# 08_LMS1_RF.net
KiCad netlist of a schematic drawn in Altium Designer
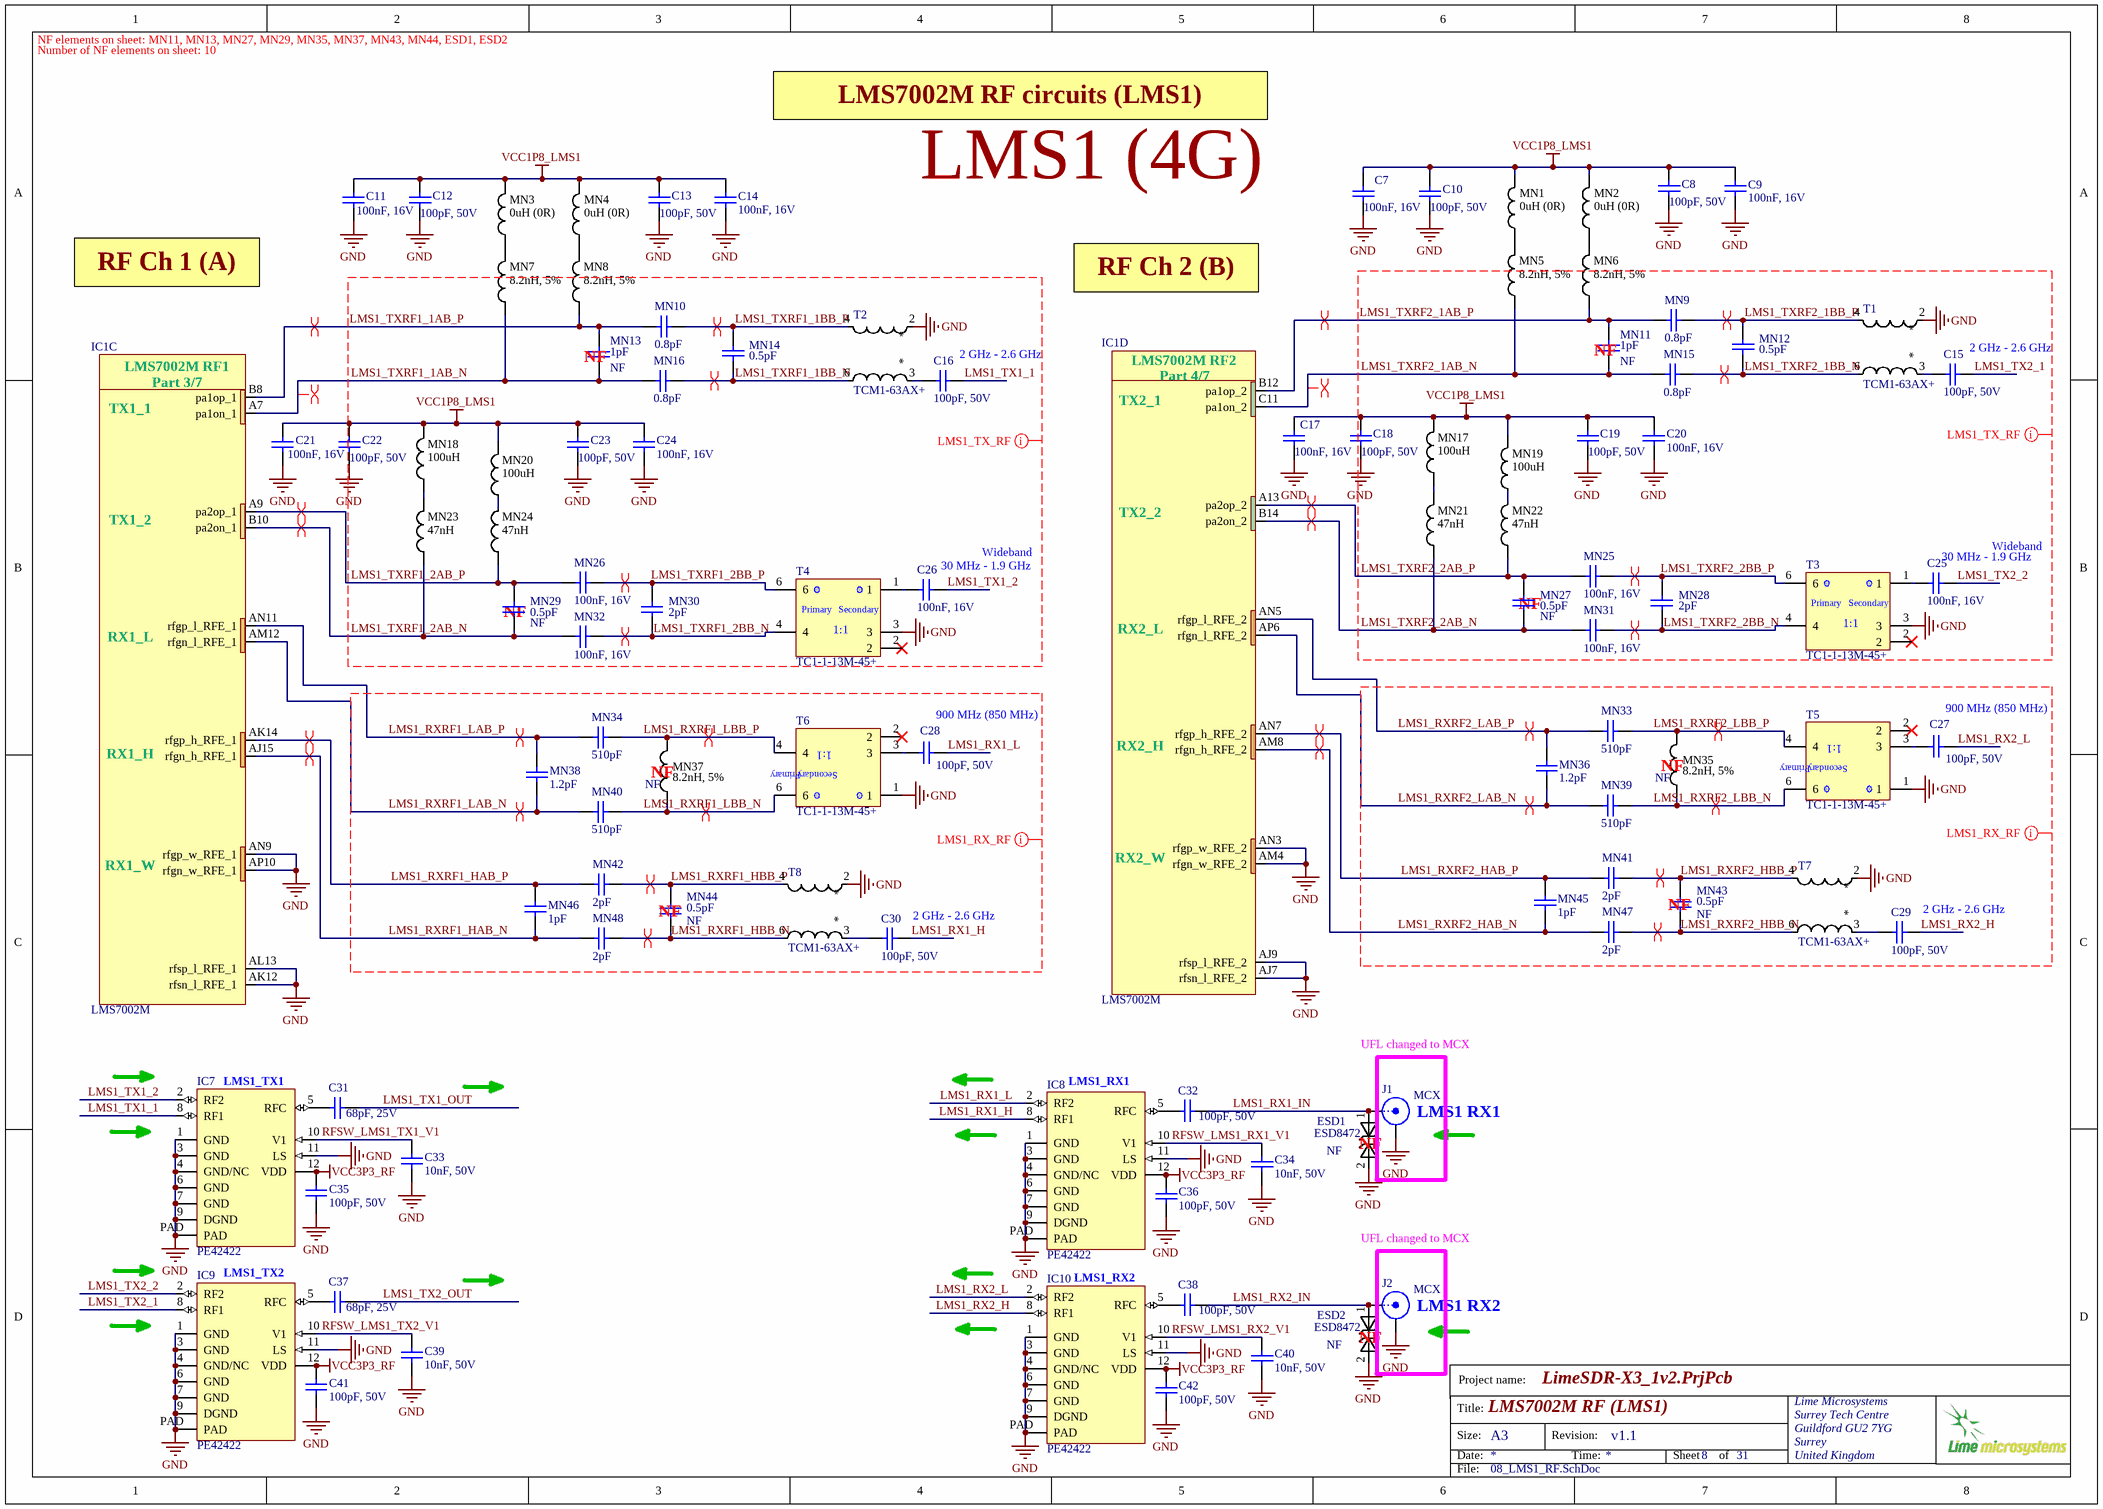
[diagram p0: 08_LMS1_RF.SchDoc]

(export (version "E")
  (design (tool "Eeschema 10.0.6"))
  (components
    (comp (ref "C7")
      (value "100nF, 16V")
      (footprint "CAP0402")
      (fields (field (name "MANUFACTURER") "Murata Electronics") (field (name "TOLERANCE") "10 %"))
      (libsource (lib "") (part "Cap_0402_2"))
    )
    (comp (ref "C8")
      (value "100pF, 50V")
      (footprint "CAP0402")
      (fields (field (name "MANUFACTURER") "Yageo") (field (name "TOLERANCE") "±5%"))
      (libsource (lib "") (part "Cap_0402_1"))
    )
    (comp (ref "C9")
      (value "100nF, 16V")
      (footprint "CAP0402")
      (fields (field (name "MANUFACTURER") "Murata Electronics") (field (name "TOLERANCE") "10 %"))
      (libsource (lib "") (part "Cap_0402_2"))
    )
    (comp (ref "C10")
      (value "100pF, 50V")
      (footprint "CAP0402")
      (fields (field (name "MANUFACTURER") "Yageo") (field (name "TOLERANCE") "±5%"))
      (libsource (lib "") (part "Cap_0402_1"))
    )
    (comp (ref "C11")
      (value "100nF, 16V")
      (footprint "CAP0402")
      (fields (field (name "MANUFACTURER") "Murata Electronics") (field (name "TOLERANCE") "10 %"))
      (libsource (lib "") (part "Cap_0402_2"))
    )
    (comp (ref "C12")
      (value "100pF, 50V")
      (footprint "CAP0402")
      (fields (field (name "MANUFACTURER") "Yageo") (field (name "TOLERANCE") "±5%"))
      (libsource (lib "") (part "Cap_0402_1"))
    )
    (comp (ref "C13")
      (value "100pF, 50V")
      (footprint "CAP0402")
      (fields (field (name "MANUFACTURER") "Yageo") (field (name "TOLERANCE") "±5%"))
      (libsource (lib "") (part "Cap_0402_1"))
    )
    (comp (ref "C14")
      (value "100nF, 16V")
      (footprint "CAP0402")
      (fields (field (name "MANUFACTURER") "Murata Electronics") (field (name "TOLERANCE") "10 %"))
      (libsource (lib "") (part "Cap_0402_2"))
    )
    (comp (ref "C15")
      (value "100pF, 50V")
      (footprint "CAP0402")
      (fields (field (name "TOLERANCE") "±5%") (field (name "MANUFACTURER") "Yageo"))
      (libsource (lib "") (part "Cap_0402_2"))
    )
    (comp (ref "C16")
      (value "100pF, 50V")
      (footprint "CAP0402")
      (fields (field (name "TOLERANCE") "±5%") (field (name "MANUFACTURER") "Yageo"))
      (libsource (lib "") (part "Cap_0402_2"))
    )
    (comp (ref "C17")
      (value "100nF, 16V")
      (footprint "CAP0402")
      (fields (field (name "MANUFACTURER") "Murata Electronics") (field (name "TOLERANCE") "10 %"))
      (libsource (lib "") (part "Cap_0402_5"))
    )
    (comp (ref "C18")
      (value "100pF, 50V")
      (footprint "CAP0402")
      (fields (field (name "MANUFACTURER") "Yageo") (field (name "TOLERANCE") "±5%"))
      (libsource (lib "") (part "Cap_0402_1"))
    )
    (comp (ref "C19")
      (value "100pF, 50V")
      (footprint "CAP0402")
      (fields (field (name "MANUFACTURER") "Yageo") (field (name "TOLERANCE") "±5%"))
      (libsource (lib "") (part "Cap_0402_1"))
    )
    (comp (ref "C20")
      (value "100nF, 16V")
      (footprint "CAP0402")
      (fields (field (name "MANUFACTURER") "Murata Electronics") (field (name "TOLERANCE") "10 %"))
      (libsource (lib "") (part "Cap_0402_5"))
    )
    (comp (ref "C21")
      (value "100nF, 16V")
      (footprint "CAP0402")
      (fields (field (name "MANUFACTURER") "Murata Electronics") (field (name "TOLERANCE") "10 %"))
      (libsource (lib "") (part "Cap_0402_5"))
    )
    (comp (ref "C22")
      (value "100pF, 50V")
      (footprint "CAP0402")
      (fields (field (name "MANUFACTURER") "Yageo") (field (name "TOLERANCE") "±5%"))
      (libsource (lib "") (part "Cap_0402_1"))
    )
    (comp (ref "C23")
      (value "100pF, 50V")
      (footprint "CAP0402")
      (fields (field (name "MANUFACTURER") "Yageo") (field (name "TOLERANCE") "±5%"))
      (libsource (lib "") (part "Cap_0402_1"))
    )
    (comp (ref "C24")
      (value "100nF, 16V")
      (footprint "CAP0402")
      (fields (field (name "MANUFACTURER") "Murata Electronics") (field (name "TOLERANCE") "10 %"))
      (libsource (lib "") (part "Cap_0402_5"))
    )
    (comp (ref "C25")
      (value "100nF, 16V")
      (footprint "CAP0402")
      (fields (field (name "MANUFACTURER") "Murata Electronics") (field (name "TOLERANCE") "10 %"))
      (libsource (lib "") (part "Cap_0402_7"))
    )
    (comp (ref "C26")
      (value "100nF, 16V")
      (footprint "CAP0402")
      (fields (field (name "MANUFACTURER") "Murata Electronics") (field (name "TOLERANCE") "10 %"))
      (libsource (lib "") (part "Cap_0402_7"))
    )
    (comp (ref "C27")
      (value "100pF, 50V")
      (footprint "CAP0402")
      (fields (field (name "TOLERANCE") "±5%") (field (name "MANUFACTURER") "Yageo"))
      (libsource (lib "") (part "Cap_0402_6"))
    )
    (comp (ref "C28")
      (value "100pF, 50V")
      (footprint "CAP0402")
      (fields (field (name "TOLERANCE") "±5%") (field (name "MANUFACTURER") "Yageo"))
      (libsource (lib "") (part "Cap_0402_6"))
    )
    (comp (ref "C29")
      (value "100pF, 50V")
      (footprint "CAP0402")
      (fields (field (name "TOLERANCE") "±5%") (field (name "MANUFACTURER") "Yageo"))
      (libsource (lib "") (part "Cap_0402_3"))
    )
    (comp (ref "C30")
      (value "100pF, 50V")
      (footprint "CAP0402")
      (fields (field (name "TOLERANCE") "±5%") (field (name "MANUFACTURER") "Yageo"))
      (libsource (lib "") (part "Cap_0402_3"))
    )
    (comp (ref "C31")
      (value "68pF, 25V")
      (footprint "CAP0402")
      (fields (field (name "TOLERANCE") "±1%") (field (name "MANUFACTURER") "Kemet"))
      (libsource (lib "") (part "Cap_0402_2"))
    )
    (comp (ref "C32")
      (value "100pF, 50V")
      (footprint "CAP0402")
      (fields (field (name "TOLERANCE") "±5%") (field (name "MANUFACTURER") "Yageo"))
      (libsource (lib "") (part "Cap_0402_4"))
    )
    (comp (ref "C33")
      (value "10nF, 50V")
      (footprint "CAP0402")
      (fields
        (field (name "MANUFACTURER") "Murata Electronics North America")
        (field (name "TOLERANCE") "±10%")
      )
      (libsource (lib "") (part "Cap_0402_2"))
    )
    (comp (ref "C34")
      (value "10nF, 50V")
      (footprint "CAP0402")
      (fields
        (field (name "MANUFACTURER") "Murata Electronics North America")
        (field (name "TOLERANCE") "±10%")
      )
      (libsource (lib "") (part "Cap_0402_10"))
    )
    (comp (ref "C35")
      (value "100pF, 50V")
      (footprint "CAP0402")
      (fields (field (name "TOLERANCE") "±5%") (field (name "MANUFACTURER") "Yageo"))
      (libsource (lib "") (part "Cap_0402_2"))
    )
    (comp (ref "C36")
      (value "100pF, 50V")
      (footprint "CAP0402")
      (fields (field (name "TOLERANCE") "±5%") (field (name "MANUFACTURER") "Yageo"))
      (libsource (lib "") (part "Cap_0402_8"))
    )
    (comp (ref "C37")
      (value "68pF, 25V")
      (footprint "CAP0402")
      (fields (field (name "TOLERANCE") "±1%") (field (name "MANUFACTURER") "Kemet"))
      (libsource (lib "") (part "Cap_0402_2"))
    )
    (comp (ref "C38")
      (value "100pF, 50V")
      (footprint "CAP0402")
      (fields (field (name "TOLERANCE") "±5%") (field (name "MANUFACTURER") "Yageo"))
      (libsource (lib "") (part "Cap_0402_4"))
    )
    (comp (ref "C39")
      (value "10nF, 50V")
      (footprint "CAP0402")
      (fields
        (field (name "MANUFACTURER") "Murata Electronics North America")
        (field (name "TOLERANCE") "±10%")
      )
      (libsource (lib "") (part "Cap_0402_2"))
    )
    (comp (ref "C40")
      (value "10nF, 50V")
      (footprint "CAP0402")
      (fields
        (field (name "MANUFACTURER") "Murata Electronics North America")
        (field (name "TOLERANCE") "±10%")
      )
      (libsource (lib "") (part "Cap_0402_10"))
    )
    (comp (ref "C41")
      (value "100pF, 50V")
      (footprint "CAP0402")
      (fields (field (name "TOLERANCE") "±5%") (field (name "MANUFACTURER") "Yageo"))
      (libsource (lib "") (part "Cap_0402_2"))
    )
    (comp (ref "C42")
      (value "100pF, 50V")
      (footprint "CAP0402")
      (fields (field (name "TOLERANCE") "±5%") (field (name "MANUFACTURER") "Yageo"))
      (libsource (lib "") (part "Cap_0402_8"))
    )
    (comp (ref "ESD1")
      (value "ESD8472")
      (footprint "ESD8472_X3DFN2")
      (fields (field (name "MANUFACTURER") "ON Semiconductor") (field (name "ASSEMBLY INFO") "NF"))
      (libsource (lib "LimeMicroAltiumLib_schLib") (part "ESD8472"))
    )
    (comp (ref "ESD2")
      (value "ESD8472")
      (footprint "ESD8472_X3DFN2")
      (fields (field (name "MANUFACTURER") "ON Semiconductor") (field (name "ASSEMBLY INFO") "NF"))
      (libsource (lib "LimeMicroAltiumLib_schLib") (part "ESD8472"))
    )
    (comp (ref "IC1")
      (value "LMS7002M")
      (footprint "LMS7002M_v5")
      (description "Schematic symbol revision 4. Default footprint - 0.31mm pad")
      (fields (field (name "MANUFACTURER") "Lime Microsystems"))
      (libsource (lib "LimeMicroAltiumLib_schLib_r04") (part "LMS7002Mr4"))
    )
    (comp (ref "IC7")
      (value "PE42422")
      (footprint "PE42422_QFN12")
      (fields (field (name "MANUFACTURER") "Peregrine Semiconductor"))
      (libsource (lib "") (part "PE42422_1"))
    )
    (comp (ref "IC8")
      (value "PE42422")
      (footprint "PE42422_QFN12")
      (fields (field (name "MANUFACTURER") "Peregrine Semiconductor"))
      (libsource (lib "LimeMicroAltiumLib_schLib") (part "PE42422"))
    )
    (comp (ref "IC9")
      (value "PE42422")
      (footprint "PE42422_QFN12")
      (fields (field (name "MANUFACTURER") "Peregrine Semiconductor"))
      (libsource (lib "") (part "PE42422_1"))
    )
    (comp (ref "IC10")
      (value "PE42422")
      (footprint "PE42422_QFN12")
      (fields (field (name "MANUFACTURER") "Peregrine Semiconductor"))
      (libsource (lib "LimeMicroAltiumLib_schLib") (part "PE42422"))
    )
    (comp (ref "J1")
      (value "MCX")
      (footprint "MCX_connector_vertical_SM")
      (description "Conn MCX RCP 0Hz to 6GHz 50Ohm Solder ST SMD Gold Over Nickel Stock")
      (fields (field (name "MANUFACTURER") "Bel Cinch"))
      (libsource (lib "LimeMicroAltiumLib_schLib") (part "RF_IF_connector"))
    )
    (comp (ref "J2")
      (value "MCX")
      (footprint "MCX_connector_vertical_SM")
      (description "Conn MCX RCP 0Hz to 6GHz 50Ohm Solder ST SMD Gold Over Nickel Stock")
      (fields (field (name "MANUFACTURER") "Bel Cinch"))
      (libsource (lib "LimeMicroAltiumLib_schLib") (part "RF_IF_connector"))
    )
    (comp (ref "MN1")
      (value "0uH (0R)")
      (footprint "RES0603")
      (fields
        (field (name "MANUFACTURER") "Panasonic Electronic Components")
        (field (name "MANUFACTURER PART NUMBER") "ERJ-3GEY0R00V")
        (field (name "TOLERANCE") "Jumper")
      )
      (libsource (lib "LimeMicroAltiumLib_schLib") (part "Inductor_0603"))
    )
    (comp (ref "MN2")
      (value "0uH (0R)")
      (footprint "RES0603")
      (fields
        (field (name "MANUFACTURER") "Panasonic Electronic Components")
        (field (name "MANUFACTURER PART NUMBER") "ERJ-3GEY0R00V")
        (field (name "TOLERANCE") "Jumper")
      )
      (libsource (lib "LimeMicroAltiumLib_schLib") (part "Inductor_0603"))
    )
    (comp (ref "MN3")
      (value "0uH (0R)")
      (footprint "RES0603")
      (fields
        (field (name "MANUFACTURER") "Panasonic Electronic Components")
        (field (name "MANUFACTURER PART NUMBER") "ERJ-3GEY0R00V")
        (field (name "TOLERANCE") "Jumper")
      )
      (libsource (lib "LimeMicroAltiumLib_schLib") (part "Inductor_0603"))
    )
    (comp (ref "MN4")
      (value "0uH (0R)")
      (footprint "RES0603")
      (fields
        (field (name "MANUFACTURER") "Panasonic Electronic Components")
        (field (name "MANUFACTURER PART NUMBER") "ERJ-3GEY0R00V")
        (field (name "TOLERANCE") "Jumper")
      )
      (libsource (lib "LimeMicroAltiumLib_schLib") (part "Inductor_0603"))
    )
    (comp (ref "MN5")
      (value "8.2nH, 5%")
      (footprint "RES0402")
      (fields (field (name "MANUFACTURER") "COILCRAFT"))
      (libsource (lib "") (part "Inductor_0603_1"))
    )
    (comp (ref "MN6")
      (value "8.2nH, 5%")
      (footprint "RES0402")
      (fields (field (name "MANUFACTURER") "COILCRAFT"))
      (libsource (lib "") (part "Inductor_0603_1"))
    )
    (comp (ref "MN7")
      (value "8.2nH, 5%")
      (footprint "RES0402")
      (fields (field (name "MANUFACTURER") "COILCRAFT"))
      (libsource (lib "") (part "Inductor_0603_1"))
    )
    (comp (ref "MN8")
      (value "8.2nH, 5%")
      (footprint "RES0402")
      (fields (field (name "MANUFACTURER") "COILCRAFT"))
      (libsource (lib "") (part "Inductor_0603_1"))
    )
    (comp (ref "MN9")
      (value "0.8pF")
      (footprint "CAP0402")
      (fields
        (field (name "TOLERANCE") "±0.1pF")
        (field (name "MANUFACTURER") "Murata Electronics North America")
        (field (name "MANUFACTURER PART NUMBER") "GRM1555C1HR80BA01D")
      )
      (libsource (lib "LimeMicroAltiumLib_schLib") (part "Cap_0402"))
    )
    (comp (ref "MN10")
      (value "0.8pF")
      (footprint "CAP0402")
      (fields
        (field (name "TOLERANCE") "±0.1pF")
        (field (name "MANUFACTURER") "Murata Electronics North America")
        (field (name "MANUFACTURER PART NUMBER") "GRM1555C1HR80BA01D")
      )
      (libsource (lib "LimeMicroAltiumLib_schLib") (part "Cap_0402"))
    )
    (comp (ref "MN11")
      (value "1pF")
      (footprint "CAP0402")
      (fields
        (field (name "ASSEMBLY INFO") "NF")
        (field (name "MANUFACTURER") "TDK Corporation")
        (field (name "TOLERANCE") "±0.1pF")
      )
      (libsource (lib "") (part "Cap_0402_6"))
    )
    (comp (ref "MN12")
      (value "0.5pF")
      (footprint "CAP0402")
      (fields (field (name "TOLERANCE") "±0.25pF") (field (name "MANUFACTURER") "Yageo"))
      (libsource (lib "") (part "Cap_0402_9"))
    )
    (comp (ref "MN13")
      (value "1pF")
      (footprint "CAP0402")
      (fields
        (field (name "ASSEMBLY INFO") "NF")
        (field (name "MANUFACTURER") "TDK Corporation")
        (field (name "TOLERANCE") "±0.1pF")
      )
      (libsource (lib "") (part "Cap_0402_6"))
    )
    (comp (ref "MN14")
      (value "0.5pF")
      (footprint "CAP0402")
      (fields (field (name "TOLERANCE") "±0.25pF") (field (name "MANUFACTURER") "Yageo"))
      (libsource (lib "") (part "Cap_0402_9"))
    )
    (comp (ref "MN15")
      (value "0.8pF")
      (footprint "CAP0402")
      (fields
        (field (name "TOLERANCE") "±0.1pF")
        (field (name "MANUFACTURER") "Murata Electronics North America")
        (field (name "MANUFACTURER PART NUMBER") "GRM1555C1HR80BA01D")
      )
      (libsource (lib "LimeMicroAltiumLib_schLib") (part "Cap_0402"))
    )
    (comp (ref "MN16")
      (value "0.8pF")
      (footprint "CAP0402")
      (fields
        (field (name "TOLERANCE") "±0.1pF")
        (field (name "MANUFACTURER") "Murata Electronics North America")
        (field (name "MANUFACTURER PART NUMBER") "GRM1555C1HR80BA01D")
      )
      (libsource (lib "LimeMicroAltiumLib_schLib") (part "Cap_0402"))
    )
    (comp (ref "MN17")
      (value "100uH")
      (footprint "RES0603")
      (fields
        (field (name "MANUFACTURER") "TDK Corporation")
        (field (name "MANUFACTURER PART NUMBER") "GLFR1608T101M-LR")
        (field (name "TOLERANCE") "±20%")
      )
      (libsource (lib "LimeMicroAltiumLib_schLib") (part "Inductor_0603"))
    )
    (comp (ref "MN18")
      (value "100uH")
      (footprint "RES0603")
      (fields
        (field (name "MANUFACTURER") "TDK Corporation")
        (field (name "MANUFACTURER PART NUMBER") "GLFR1608T101M-LR")
        (field (name "TOLERANCE") "±20%")
      )
      (libsource (lib "LimeMicroAltiumLib_schLib") (part "Inductor_0603"))
    )
    (comp (ref "MN19")
      (value "100uH")
      (footprint "RES0603")
      (fields
        (field (name "MANUFACTURER") "TDK Corporation")
        (field (name "MANUFACTURER PART NUMBER") "GLFR1608T101M-LR")
        (field (name "TOLERANCE") "±20%")
      )
      (libsource (lib "LimeMicroAltiumLib_schLib") (part "Inductor_0603"))
    )
    (comp (ref "MN20")
      (value "100uH")
      (footprint "RES0603")
      (fields
        (field (name "MANUFACTURER") "TDK Corporation")
        (field (name "MANUFACTURER PART NUMBER") "GLFR1608T101M-LR")
        (field (name "TOLERANCE") "±20%")
      )
      (libsource (lib "LimeMicroAltiumLib_schLib") (part "Inductor_0603"))
    )
    (comp (ref "MN21")
      (value "47nH")
      (footprint "RES0402")
      (fields (field (name "MANUFACTURER") "COILCRAFT"))
      (libsource (lib "") (part "Inductor_0603_2"))
    )
    (comp (ref "MN22")
      (value "47nH")
      (footprint "RES0402")
      (fields (field (name "MANUFACTURER") "COILCRAFT"))
      (libsource (lib "") (part "Inductor_0603_2"))
    )
    (comp (ref "MN23")
      (value "47nH")
      (footprint "RES0402")
      (fields (field (name "MANUFACTURER") "COILCRAFT"))
      (libsource (lib "") (part "Inductor_0603_2"))
    )
    (comp (ref "MN24")
      (value "47nH")
      (footprint "RES0402")
      (fields (field (name "MANUFACTURER") "COILCRAFT"))
      (libsource (lib "") (part "Inductor_0603_2"))
    )
    (comp (ref "MN25")
      (value "100nF, 16V")
      (footprint "CAP0402")
      (fields (field (name "MANUFACTURER") "Murata Electronics") (field (name "TOLERANCE") "10 %"))
      (libsource (lib "") (part "Cap_0402_1"))
    )
    (comp (ref "MN26")
      (value "100nF, 16V")
      (footprint "CAP0402")
      (fields (field (name "MANUFACTURER") "Murata Electronics") (field (name "TOLERANCE") "10 %"))
      (libsource (lib "") (part "Cap_0402_1"))
    )
    (comp (ref "MN27")
      (value "0.5pF")
      (footprint "CAP0402")
      (fields
        (field (name "ASSEMBLY INFO") "NF")
        (field (name "TOLERANCE") "±0.25pF")
        (field (name "MANUFACTURER") "Yageo")
      )
      (libsource (lib "") (part "Cap_0402_5"))
    )
    (comp (ref "MN28")
      (value "2pF")
      (footprint "CAP0402")
      (fields (field (name "MANUFACTURER PART NUMBER") "04025U2R0BAT2A") (field (name "MANUFACTURER") "AVX"))
      (libsource (lib "") (part "Cap_0402_5"))
    )
    (comp (ref "MN29")
      (value "0.5pF")
      (footprint "CAP0402")
      (fields
        (field (name "ASSEMBLY INFO") "NF")
        (field (name "TOLERANCE") "±0.25pF")
        (field (name "MANUFACTURER") "Yageo")
      )
      (libsource (lib "") (part "Cap_0402_5"))
    )
    (comp (ref "MN30")
      (value "2pF")
      (footprint "CAP0402")
      (fields (field (name "MANUFACTURER PART NUMBER") "04025U2R0BAT2A") (field (name "MANUFACTURER") "AVX"))
      (libsource (lib "") (part "Cap_0402_5"))
    )
    (comp (ref "MN31")
      (value "100nF, 16V")
      (footprint "CAP0402")
      (fields (field (name "MANUFACTURER") "Murata Electronics") (field (name "TOLERANCE") "10 %"))
      (libsource (lib "") (part "Cap_0402_9"))
    )
    (comp (ref "MN32")
      (value "100nF, 16V")
      (footprint "CAP0402")
      (fields (field (name "MANUFACTURER") "Murata Electronics") (field (name "TOLERANCE") "10 %"))
      (libsource (lib "") (part "Cap_0402_9"))
    )
    (comp (ref "MN33")
      (value "510pF")
      (footprint "CAP0402")
      (fields
        (field (name "TOLERANCE") "±5%")
        (field (name "MANUFACTURER") "Murata Electronics North America")
      )
      (libsource (lib "") (part "Cap_0402_2"))
    )
    (comp (ref "MN34")
      (value "510pF")
      (footprint "CAP0402")
      (fields
        (field (name "TOLERANCE") "±5%")
        (field (name "MANUFACTURER") "Murata Electronics North America")
      )
      (libsource (lib "") (part "Cap_0402_2"))
    )
    (comp (ref "MN35")
      (value "8.2nH, 5%")
      (footprint "RES0402")
      (fields (field (name "MANUFACTURER") "COILCRAFT") (field (name "ASSEMBLY INFO") "NF"))
      (libsource (lib "") (part "Inductor_0603_2"))
    )
    (comp (ref "MN36")
      (value "1.2pF")
      (footprint "CAP0402")
      (fields
        (field (name "MANUFACTURER") "Murata Electronics North America")
        (field (name "TOLERANCE") "±0.25pF")
      )
      (libsource (lib "") (part "Cap_0402_2"))
    )
    (comp (ref "MN37")
      (value "8.2nH, 5%")
      (footprint "RES0402")
      (fields (field (name "MANUFACTURER") "COILCRAFT") (field (name "ASSEMBLY INFO") "NF"))
      (libsource (lib "") (part "Inductor_0603_2"))
    )
    (comp (ref "MN38")
      (value "1.2pF")
      (footprint "CAP0402")
      (fields
        (field (name "MANUFACTURER") "Murata Electronics North America")
        (field (name "TOLERANCE") "±0.25pF")
      )
      (libsource (lib "") (part "Cap_0402_2"))
    )
    (comp (ref "MN39")
      (value "510pF")
      (footprint "CAP0402")
      (fields
        (field (name "TOLERANCE") "±5%")
        (field (name "MANUFACTURER") "Murata Electronics North America")
      )
      (libsource (lib "") (part "Cap_0402_2"))
    )
    (comp (ref "MN40")
      (value "510pF")
      (footprint "CAP0402")
      (fields
        (field (name "TOLERANCE") "±5%")
        (field (name "MANUFACTURER") "Murata Electronics North America")
      )
      (libsource (lib "") (part "Cap_0402_2"))
    )
    (comp (ref "MN41")
      (value "2pF")
      (footprint "CAP0402")
      (fields (field (name "MANUFACTURER PART NUMBER") "04025U2R0BAT2A") (field (name "MANUFACTURER") "AVX"))
      (libsource (lib "LimeMicroAltiumLib_schLib") (part "Cap_0402"))
    )
    (comp (ref "MN42")
      (value "2pF")
      (footprint "CAP0402")
      (fields (field (name "MANUFACTURER PART NUMBER") "04025U2R0BAT2A") (field (name "MANUFACTURER") "AVX"))
      (libsource (lib "LimeMicroAltiumLib_schLib") (part "Cap_0402"))
    )
    (comp (ref "MN43")
      (value "0.5pF")
      (footprint "CAP0402")
      (fields
        (field (name "ASSEMBLY INFO") "NF")
        (field (name "TOLERANCE") "±0.25pF")
        (field (name "MANUFACTURER") "Yageo")
      )
      (libsource (lib "LimeMicroAltiumLib_schLib") (part "Cap_0402"))
    )
    (comp (ref "MN44")
      (value "0.5pF")
      (footprint "CAP0402")
      (fields
        (field (name "ASSEMBLY INFO") "NF")
        (field (name "TOLERANCE") "±0.25pF")
        (field (name "MANUFACTURER") "Yageo")
      )
      (libsource (lib "LimeMicroAltiumLib_schLib") (part "Cap_0402"))
    )
    (comp (ref "MN45")
      (value "1pF")
      (footprint "CAP0402")
      (fields (field (name "MANUFACTURER") "TDK Corporation") (field (name "TOLERANCE") "±0.1pF"))
      (libsource (lib "LimeMicroAltiumLib_schLib") (part "Cap_0402"))
    )
    (comp (ref "MN46")
      (value "1pF")
      (footprint "CAP0402")
      (fields (field (name "MANUFACTURER") "TDK Corporation") (field (name "TOLERANCE") "±0.1pF"))
      (libsource (lib "LimeMicroAltiumLib_schLib") (part "Cap_0402"))
    )
    (comp (ref "MN47")
      (value "2pF")
      (footprint "CAP0402")
      (fields (field (name "MANUFACTURER PART NUMBER") "04025U2R0BAT2A") (field (name "MANUFACTURER") "AVX"))
      (libsource (lib "LimeMicroAltiumLib_schLib") (part "Cap_0402"))
    )
    (comp (ref "MN48")
      (value "2pF")
      (footprint "CAP0402")
      (fields (field (name "MANUFACTURER PART NUMBER") "04025U2R0BAT2A") (field (name "MANUFACTURER") "AVX"))
      (libsource (lib "LimeMicroAltiumLib_schLib") (part "Cap_0402"))
    )
    (comp (ref "T1")
      (value "TCM1-63AX+")
      (footprint "TCM1-63AX+_v2")
      (fields (field (name "MANUFACTURER") "Mini-circuits"))
      (libsource (lib "") (part "Balun_v2_1"))
    )
    (comp (ref "T2")
      (value "TCM1-63AX+")
      (footprint "TCM1-63AX+_v2")
      (fields (field (name "MANUFACTURER") "Mini-circuits"))
      (libsource (lib "") (part "Balun_v2_1"))
    )
    (comp (ref "T3")
      (value "TC1-1-13M-45+")
      (footprint "TC1-1-13MA+_JA4220-AL_")
      (fields (field (name "MANUFACTURER") "Minicircuits"))
      (libsource (lib "") (part "TC1-1-13M+_1"))
    )
    (comp (ref "T4")
      (value "TC1-1-13M-45+")
      (footprint "TC1-1-13MA+_JA4220-AL_")
      (fields (field (name "MANUFACTURER") "Minicircuits"))
      (libsource (lib "") (part "TC1-1-13M+_1"))
    )
    (comp (ref "T5")
      (value "TC1-1-13M-45+")
      (footprint "TC1-1-13MA+_JA4220-AL_")
      (fields (field (name "MANUFACTURER") "Minicircuits"))
      (libsource (lib "LimeMicroAltiumLib_schLib") (part "TC1-1-13M+"))
    )
    (comp (ref "T6")
      (value "TC1-1-13M-45+")
      (footprint "TC1-1-13MA+_JA4220-AL_")
      (fields (field (name "MANUFACTURER") "Minicircuits"))
      (libsource (lib "LimeMicroAltiumLib_schLib") (part "TC1-1-13M+"))
    )
    (comp (ref "T7")
      (value "TCM1-63AX+")
      (footprint "TCM1-63AX+_v2")
      (fields (field (name "MANUFACTURER") "Mini-circuits"))
      (libsource (lib "LimeMicroAltiumLib_schLib") (part "Balun_v2"))
    )
    (comp (ref "T8")
      (value "TCM1-63AX+")
      (footprint "TCM1-63AX+_v2")
      (fields (field (name "MANUFACTURER") "Mini-circuits"))
      (libsource (lib "LimeMicroAltiumLib_schLib") (part "Balun_v2"))
    )
  )
  (nets
    (net (code "1") (name "/LMS1_RX1_H") (class "Default")
      (node (ref "C30") (pin "1") (pinfunction "1_1") (pintype "passive"))
      (node (ref "IC8") (pin "8") (pinfunction "RF1_8") (pintype "bidirectional"))
    )
    (net (code "2") (name "/LMS1_RX1_IN") (class "Default")
      (node (ref "C32") (pin "1") (pinfunction "1_1") (pintype "passive"))
      (node (ref "ESD1") (pin "1") (pinfunction "1_1") (pintype "passive"))
      (node (ref "J1") (pin "1") (pinfunction "X_1") (pintype "passive"))
    )
    (net (code "3") (name "/LMS1_RX1_L") (class "Default")
      (node (ref "C28") (pin "1") (pinfunction "1_1") (pintype "passive"))
      (node (ref "IC8") (pin "2") (pinfunction "RF2_2") (pintype "bidirectional"))
    )
    (net (code "4") (name "/LMS1_RX2_H") (class "Default")
      (node (ref "C29") (pin "1") (pinfunction "1_1") (pintype "passive"))
      (node (ref "IC10") (pin "8") (pinfunction "RF1_8") (pintype "bidirectional"))
    )
    (net (code "5") (name "/LMS1_RX2_IN") (class "Default")
      (node (ref "C38") (pin "1") (pinfunction "1_1") (pintype "passive"))
      (node (ref "ESD2") (pin "1") (pinfunction "1_1") (pintype "passive"))
      (node (ref "J2") (pin "1") (pinfunction "X_1") (pintype "passive"))
    )
    (net (code "6") (name "/LMS1_RX2_L") (class "Default")
      (node (ref "C27") (pin "1") (pinfunction "1_1") (pintype "passive"))
      (node (ref "IC10") (pin "2") (pinfunction "RF2_2") (pintype "bidirectional"))
    )
    (net (code "7") (name "/LMS1_RXRF1_HAB_N") (class "Default")
      (node (ref "IC1") (pin "AJ15") (pinfunction "rfgn_h_RFE_1_AJ15") (pintype "passive"))
      (node (ref "MN46") (pin "1") (pinfunction "1_1") (pintype "passive"))
      (node (ref "MN48") (pin "2") (pinfunction "2_2") (pintype "passive"))
    )
    (net (code "8") (name "/LMS1_RXRF1_HAB_P") (class "Default")
      (node (ref "IC1") (pin "AK14") (pinfunction "rfgp_h_RFE_1_AK14") (pintype "passive"))
      (node (ref "MN42") (pin "2") (pinfunction "2_2") (pintype "passive"))
      (node (ref "MN46") (pin "2") (pinfunction "2_2") (pintype "passive"))
    )
    (net (code "9") (name "/LMS1_RXRF1_HBB_N") (class "Default")
      (node (ref "MN44") (pin "1") (pinfunction "1_1") (pintype "passive"))
      (node (ref "MN48") (pin "1") (pinfunction "1_1") (pintype "passive"))
      (node (ref "T8") (pin "6") (pinfunction "6_6") (pintype "passive"))
    )
    (net (code "10") (name "/LMS1_RXRF1_HBB_P") (class "Default")
      (node (ref "MN42") (pin "1") (pinfunction "1_1") (pintype "passive"))
      (node (ref "MN44") (pin "2") (pinfunction "2_2") (pintype "passive"))
      (node (ref "T8") (pin "4") (pinfunction "4_4") (pintype "passive"))
    )
    (net (code "11") (name "/LMS1_RXRF1_LAB_N") (class "Default")
      (node (ref "IC1") (pin "AM12") (pinfunction "rfgn_l_RFE_1_AM12") (pintype "passive"))
      (node (ref "MN38") (pin "1") (pinfunction "1_1") (pintype "passive"))
      (node (ref "MN40") (pin "2") (pinfunction "2_2") (pintype "passive"))
    )
    (net (code "12") (name "/LMS1_RXRF1_LAB_P") (class "Default")
      (node (ref "IC1") (pin "AN11") (pinfunction "rfgp_l_RFE_1_AN11") (pintype "passive"))
      (node (ref "MN34") (pin "2") (pinfunction "2_2") (pintype "passive"))
      (node (ref "MN38") (pin "2") (pinfunction "2_2") (pintype "passive"))
    )
    (net (code "13") (name "/LMS1_RXRF1_LBB_N") (class "Default")
      (node (ref "MN37") (pin "1") (pinfunction "1_1") (pintype "passive"))
      (node (ref "MN40") (pin "1") (pinfunction "1_1") (pintype "passive"))
      (node (ref "T6") (pin "6") (pinfunction "6_6") (pintype "passive"))
    )
    (net (code "14") (name "/LMS1_RXRF1_LBB_P") (class "Default")
      (node (ref "MN34") (pin "1") (pinfunction "1_1") (pintype "passive"))
      (node (ref "MN37") (pin "2") (pinfunction "2_2") (pintype "passive"))
      (node (ref "T6") (pin "4") (pinfunction "4_4") (pintype "passive"))
    )
    (net (code "15") (name "/LMS1_RXRF2_HAB_N") (class "Default")
      (node (ref "IC1") (pin "AM8") (pinfunction "rfgn_h_RFE_2_AM8") (pintype "passive"))
      (node (ref "MN45") (pin "1") (pinfunction "1_1") (pintype "passive"))
      (node (ref "MN47") (pin "2") (pinfunction "2_2") (pintype "passive"))
    )
    (net (code "16") (name "/LMS1_RXRF2_HAB_P") (class "Default")
      (node (ref "IC1") (pin "AN7") (pinfunction "rfgp_h_RFE_2_AN7") (pintype "passive"))
      (node (ref "MN41") (pin "2") (pinfunction "2_2") (pintype "passive"))
      (node (ref "MN45") (pin "2") (pinfunction "2_2") (pintype "passive"))
    )
    (net (code "17") (name "/LMS1_RXRF2_HBB_N") (class "Default")
      (node (ref "MN43") (pin "1") (pinfunction "1_1") (pintype "passive"))
      (node (ref "MN47") (pin "1") (pinfunction "1_1") (pintype "passive"))
      (node (ref "T7") (pin "6") (pinfunction "6_6") (pintype "passive"))
    )
    (net (code "18") (name "/LMS1_RXRF2_HBB_P") (class "Default")
      (node (ref "MN41") (pin "1") (pinfunction "1_1") (pintype "passive"))
      (node (ref "MN43") (pin "2") (pinfunction "2_2") (pintype "passive"))
      (node (ref "T7") (pin "4") (pinfunction "4_4") (pintype "passive"))
    )
    (net (code "19") (name "/LMS1_RXRF2_LAB_N") (class "Default")
      (node (ref "IC1") (pin "AP6") (pinfunction "rfgn_l_RFE_2_AP6") (pintype "passive"))
      (node (ref "MN36") (pin "1") (pinfunction "1_1") (pintype "passive"))
      (node (ref "MN39") (pin "2") (pinfunction "2_2") (pintype "passive"))
    )
    (net (code "20") (name "/LMS1_RXRF2_LAB_P") (class "Default")
      (node (ref "IC1") (pin "AN5") (pinfunction "rfgp_l_RFE_2_AN5") (pintype "passive"))
      (node (ref "MN33") (pin "2") (pinfunction "2_2") (pintype "passive"))
      (node (ref "MN36") (pin "2") (pinfunction "2_2") (pintype "passive"))
    )
    (net (code "21") (name "/LMS1_RXRF2_LBB_N") (class "Default")
      (node (ref "MN35") (pin "1") (pinfunction "1_1") (pintype "passive"))
      (node (ref "MN39") (pin "1") (pinfunction "1_1") (pintype "passive"))
      (node (ref "T5") (pin "6") (pinfunction "6_6") (pintype "passive"))
    )
    (net (code "22") (name "/LMS1_RXRF2_LBB_P") (class "Default")
      (node (ref "MN33") (pin "1") (pinfunction "1_1") (pintype "passive"))
      (node (ref "MN35") (pin "2") (pinfunction "2_2") (pintype "passive"))
      (node (ref "T5") (pin "4") (pinfunction "4_4") (pintype "passive"))
    )
    (net (code "23") (name "/LMS1_TX1_1") (class "Default")
      (node (ref "C16") (pin "1") (pinfunction "1_1") (pintype "passive"))
      (node (ref "IC7") (pin "8") (pinfunction "RF1_8") (pintype "bidirectional"))
    )
    (net (code "24") (name "/LMS1_TX1_2") (class "Default")
      (node (ref "C26") (pin "1") (pinfunction "1_1") (pintype "passive"))
      (node (ref "IC7") (pin "2") (pinfunction "RF2_2") (pintype "bidirectional"))
    )
    (net (code "25") (name "/LMS1_TX1_OUT") (class "Default")
      (node (ref "C31") (pin "2") (pinfunction "2_2") (pintype "passive"))
    )
    (net (code "26") (name "/LMS1_TX2_1") (class "Default")
      (node (ref "C15") (pin "1") (pinfunction "1_1") (pintype "passive"))
      (node (ref "IC9") (pin "8") (pinfunction "RF1_8") (pintype "bidirectional"))
    )
    (net (code "27") (name "/LMS1_TX2_2") (class "Default")
      (node (ref "C25") (pin "1") (pinfunction "1_1") (pintype "passive"))
      (node (ref "IC9") (pin "2") (pinfunction "RF2_2") (pintype "bidirectional"))
    )
    (net (code "28") (name "/LMS1_TX2_OUT") (class "Default")
      (node (ref "C37") (pin "2") (pinfunction "2_2") (pintype "passive"))
    )
    (net (code "29") (name "/LMS1_TXRF1_1AB_N") (class "Default")
      (node (ref "IC1") (pin "A7") (pinfunction "pa1on_1_A7") (pintype "passive"))
      (node (ref "MN13") (pin "2") (pinfunction "2_2") (pintype "passive"))
      (node (ref "MN16") (pin "2") (pinfunction "2_2") (pintype "passive"))
      (node (ref "MN7") (pin "1") (pinfunction "1_1") (pintype "passive"))
    )
    (net (code "30") (name "/LMS1_TXRF1_1AB_P") (class "Default")
      (node (ref "IC1") (pin "B8") (pinfunction "pa1op_1_B8") (pintype "passive"))
      (node (ref "MN10") (pin "2") (pinfunction "2_2") (pintype "passive"))
      (node (ref "MN13") (pin "1") (pinfunction "1_1") (pintype "passive"))
      (node (ref "MN8") (pin "1") (pinfunction "1_1") (pintype "passive"))
    )
    (net (code "31") (name "/LMS1_TXRF1_1BB_N") (class "Default")
      (node (ref "MN14") (pin "1") (pinfunction "1_1") (pintype "passive"))
      (node (ref "MN16") (pin "1") (pinfunction "1_1") (pintype "passive"))
      (node (ref "T2") (pin "6") (pinfunction "6_6") (pintype "passive"))
    )
    (net (code "32") (name "/LMS1_TXRF1_1BB_P") (class "Default")
      (node (ref "MN10") (pin "1") (pinfunction "1_1") (pintype "passive"))
      (node (ref "MN14") (pin "2") (pinfunction "2_2") (pintype "passive"))
      (node (ref "T2") (pin "4") (pinfunction "4_4") (pintype "passive"))
    )
    (net (code "33") (name "/LMS1_TXRF1_2AB_N") (class "Default")
      (node (ref "IC1") (pin "B10") (pinfunction "pa2on_1_B10") (pintype "passive"))
      (node (ref "MN23") (pin "1") (pinfunction "1_1") (pintype "passive"))
      (node (ref "MN29") (pin "1") (pinfunction "1_1") (pintype "passive"))
      (node (ref "MN32") (pin "1") (pinfunction "1_1") (pintype "passive"))
    )
    (net (code "34") (name "/LMS1_TXRF1_2AB_P") (class "Default")
      (node (ref "IC1") (pin "A9") (pinfunction "pa2op_1_A9") (pintype "passive"))
      (node (ref "MN24") (pin "1") (pinfunction "1_1") (pintype "passive"))
      (node (ref "MN26") (pin "2") (pinfunction "2_2") (pintype "passive"))
      (node (ref "MN29") (pin "2") (pinfunction "2_2") (pintype "passive"))
    )
    (net (code "35") (name "/LMS1_TXRF1_2BB_N") (class "Default")
      (node (ref "MN30") (pin "1") (pinfunction "1_1") (pintype "passive"))
      (node (ref "MN32") (pin "2") (pinfunction "2_2") (pintype "passive"))
      (node (ref "T4") (pin "4") (pinfunction "4_4") (pintype "passive"))
    )
    (net (code "36") (name "/LMS1_TXRF1_2BB_P") (class "Default")
      (node (ref "MN26") (pin "1") (pinfunction "1_1") (pintype "passive"))
      (node (ref "MN30") (pin "2") (pinfunction "2_2") (pintype "passive"))
      (node (ref "T4") (pin "6") (pinfunction "6_6") (pintype "passive"))
    )
    (net (code "37") (name "/LMS1_TXRF2_1AB_N") (class "Default")
      (node (ref "IC1") (pin "C11") (pinfunction "pa1on_2_C11") (pintype "passive"))
      (node (ref "MN11") (pin "2") (pinfunction "2_2") (pintype "passive"))
      (node (ref "MN15") (pin "2") (pinfunction "2_2") (pintype "passive"))
      (node (ref "MN5") (pin "1") (pinfunction "1_1") (pintype "passive"))
    )
    (net (code "38") (name "/LMS1_TXRF2_1AB_P") (class "Default")
      (node (ref "IC1") (pin "B12") (pinfunction "pa1op_2_B12") (pintype "passive"))
      (node (ref "MN11") (pin "1") (pinfunction "1_1") (pintype "passive"))
      (node (ref "MN6") (pin "1") (pinfunction "1_1") (pintype "passive"))
      (node (ref "MN9") (pin "2") (pinfunction "2_2") (pintype "passive"))
    )
    (net (code "39") (name "/LMS1_TXRF2_1BB_N") (class "Default")
      (node (ref "MN12") (pin "1") (pinfunction "1_1") (pintype "passive"))
      (node (ref "MN15") (pin "1") (pinfunction "1_1") (pintype "passive"))
      (node (ref "T1") (pin "6") (pinfunction "6_6") (pintype "passive"))
    )
    (net (code "40") (name "/LMS1_TXRF2_1BB_P") (class "Default")
      (node (ref "MN12") (pin "2") (pinfunction "2_2") (pintype "passive"))
      (node (ref "MN9") (pin "1") (pinfunction "1_1") (pintype "passive"))
      (node (ref "T1") (pin "4") (pinfunction "4_4") (pintype "passive"))
    )
    (net (code "41") (name "/LMS1_TXRF2_2AB_N") (class "Default")
      (node (ref "IC1") (pin "B14") (pinfunction "pa2on_2_B14") (pintype "passive"))
      (node (ref "MN21") (pin "1") (pinfunction "1_1") (pintype "passive"))
      (node (ref "MN27") (pin "1") (pinfunction "1_1") (pintype "passive"))
      (node (ref "MN31") (pin "1") (pinfunction "1_1") (pintype "passive"))
    )
    (net (code "42") (name "/LMS1_TXRF2_2AB_P") (class "Default")
      (node (ref "IC1") (pin "A13") (pinfunction "pa2op_2_A13") (pintype "passive"))
      (node (ref "MN22") (pin "1") (pinfunction "1_1") (pintype "passive"))
      (node (ref "MN25") (pin "2") (pinfunction "2_2") (pintype "passive"))
      (node (ref "MN27") (pin "2") (pinfunction "2_2") (pintype "passive"))
    )
    (net (code "43") (name "/LMS1_TXRF2_2BB_N") (class "Default")
      (node (ref "MN28") (pin "1") (pinfunction "1_1") (pintype "passive"))
      (node (ref "MN31") (pin "2") (pinfunction "2_2") (pintype "passive"))
      (node (ref "T3") (pin "4") (pinfunction "4_4") (pintype "passive"))
    )
    (net (code "44") (name "/LMS1_TXRF2_2BB_P") (class "Default")
      (node (ref "MN25") (pin "1") (pinfunction "1_1") (pintype "passive"))
      (node (ref "MN28") (pin "2") (pinfunction "2_2") (pintype "passive"))
      (node (ref "T3") (pin "6") (pinfunction "6_6") (pintype "passive"))
    )
    (net (code "45") (name "/RFSW_LMS1_RX1_V1") (class "Default")
      (node (ref "C34") (pin "1") (pinfunction "1_1") (pintype "passive"))
      (node (ref "IC8") (pin "10") (pinfunction "V1_10") (pintype "input"))
    )
    (net (code "46") (name "/RFSW_LMS1_RX2_V1") (class "Default")
      (node (ref "C40") (pin "1") (pinfunction "1_1") (pintype "passive"))
      (node (ref "IC10") (pin "10") (pinfunction "V1_10") (pintype "input"))
    )
    (net (code "47") (name "/RFSW_LMS1_TX1_V1") (class "Default")
      (node (ref "C33") (pin "1") (pinfunction "1_1") (pintype "passive"))
      (node (ref "IC7") (pin "10") (pinfunction "V1_10") (pintype "input"))
    )
    (net (code "48") (name "/RFSW_LMS1_TX2_V1") (class "Default")
      (node (ref "C39") (pin "1") (pinfunction "1_1") (pintype "passive"))
      (node (ref "IC9") (pin "10") (pinfunction "V1_10") (pintype "input"))
    )
    (net (code "49") (name "GND") (class "Default")
      (node (ref "C10") (pin "1") (pinfunction "1_1") (pintype "passive"))
      (node (ref "C11") (pin "1") (pinfunction "1_1") (pintype "passive"))
      (node (ref "C12") (pin "1") (pinfunction "1_1") (pintype "passive"))
      (node (ref "C13") (pin "1") (pinfunction "1_1") (pintype "passive"))
      (node (ref "C14") (pin "1") (pinfunction "1_1") (pintype "passive"))
      (node (ref "C17") (pin "1") (pinfunction "1_1") (pintype "passive"))
      (node (ref "C18") (pin "1") (pinfunction "1_1") (pintype "passive"))
      (node (ref "C19") (pin "1") (pinfunction "1_1") (pintype "passive"))
      (node (ref "C20") (pin "1") (pinfunction "1_1") (pintype "passive"))
      (node (ref "C21") (pin "1") (pinfunction "1_1") (pintype "passive"))
      (node (ref "C22") (pin "1") (pinfunction "1_1") (pintype "passive"))
      (node (ref "C23") (pin "1") (pinfunction "1_1") (pintype "passive"))
      (node (ref "C24") (pin "1") (pinfunction "1_1") (pintype "passive"))
      (node (ref "C33") (pin "2") (pinfunction "2_2") (pintype "passive"))
      (node (ref "C34") (pin "2") (pinfunction "2_2") (pintype "passive"))
      (node (ref "C35") (pin "1") (pinfunction "1_1") (pintype "passive"))
      (node (ref "C36") (pin "1") (pinfunction "1_1") (pintype "passive"))
      (node (ref "C39") (pin "2") (pinfunction "2_2") (pintype "passive"))
      (node (ref "C40") (pin "2") (pinfunction "2_2") (pintype "passive"))
      (node (ref "C41") (pin "1") (pinfunction "1_1") (pintype "passive"))
      (node (ref "C42") (pin "1") (pinfunction "1_1") (pintype "passive"))
      (node (ref "C7") (pin "1") (pinfunction "1_1") (pintype "passive"))
      (node (ref "C8") (pin "1") (pinfunction "1_1") (pintype "passive"))
      (node (ref "C9") (pin "1") (pinfunction "1_1") (pintype "passive"))
      (node (ref "ESD1") (pin "2") (pinfunction "2_2") (pintype "passive"))
      (node (ref "ESD2") (pin "2") (pinfunction "2_2") (pintype "passive"))
      (node (ref "IC1") (pin "AJ7") (pinfunction "rfsn_l_RFE_2_AJ7") (pintype "passive"))
      (node (ref "IC1") (pin "AJ9") (pinfunction "rfsp_l_RFE_2_AJ9") (pintype "passive"))
      (node (ref "IC1") (pin "AK12") (pinfunction "rfsn_l_RFE_1_AK12") (pintype "passive"))
      (node (ref "IC1") (pin "AL13") (pinfunction "rfsp_l_RFE_1_AL13") (pintype "passive"))
      (node (ref "IC1") (pin "AM4") (pinfunction "rfgn_w_RFE_2_AM4") (pintype "passive"))
      (node (ref "IC1") (pin "AN3") (pinfunction "rfgp_w_RFE_2_AN3") (pintype "passive"))
      (node (ref "IC1") (pin "AN9") (pinfunction "rfgp_w_RFE_1_AN9") (pintype "passive"))
      (node (ref "IC1") (pin "AP10") (pinfunction "rfgn_w_RFE_1_AP10") (pintype "passive"))
      (node (ref "IC10") (pin "1") (pinfunction "GND_1") (pintype "passive"))
      (node (ref "IC10") (pin "11") (pinfunction "LS_11") (pintype "input"))
      (node (ref "IC10") (pin "3") (pinfunction "GND_3") (pintype "passive"))
      (node (ref "IC10") (pin "4") (pinfunction "GND/NC_4") (pintype "passive"))
      (node (ref "IC10") (pin "6") (pinfunction "GND_6") (pintype "passive"))
      (node (ref "IC10") (pin "7") (pinfunction "GND_7") (pintype "passive"))
      (node (ref "IC10") (pin "9") (pinfunction "DGND_9") (pintype "passive"))
      (node (ref "IC10") (pin "PAD") (pinfunction "PAD_PAD") (pintype "passive"))
      (node (ref "IC7") (pin "1") (pinfunction "GND_1") (pintype "passive"))
      (node (ref "IC7") (pin "11") (pinfunction "LS_11") (pintype "input"))
      (node (ref "IC7") (pin "3") (pinfunction "GND_3") (pintype "passive"))
      (node (ref "IC7") (pin "4") (pinfunction "GND/NC_4") (pintype "passive"))
      (node (ref "IC7") (pin "6") (pinfunction "GND_6") (pintype "passive"))
      (node (ref "IC7") (pin "7") (pinfunction "GND_7") (pintype "passive"))
      (node (ref "IC7") (pin "9") (pinfunction "DGND_9") (pintype "passive"))
      (node (ref "IC7") (pin "PAD") (pinfunction "PAD_PAD") (pintype "passive"))
      (node (ref "IC8") (pin "1") (pinfunction "GND_1") (pintype "passive"))
      (node (ref "IC8") (pin "11") (pinfunction "LS_11") (pintype "input"))
      (node (ref "IC8") (pin "3") (pinfunction "GND_3") (pintype "passive"))
      (node (ref "IC8") (pin "4") (pinfunction "GND/NC_4") (pintype "passive"))
      (node (ref "IC8") (pin "6") (pinfunction "GND_6") (pintype "passive"))
      (node (ref "IC8") (pin "7") (pinfunction "GND_7") (pintype "passive"))
      (node (ref "IC8") (pin "9") (pinfunction "DGND_9") (pintype "passive"))
      (node (ref "IC8") (pin "PAD") (pinfunction "PAD_PAD") (pintype "passive"))
      (node (ref "IC9") (pin "1") (pinfunction "GND_1") (pintype "passive"))
      (node (ref "IC9") (pin "11") (pinfunction "LS_11") (pintype "input"))
      (node (ref "IC9") (pin "3") (pinfunction "GND_3") (pintype "passive"))
      (node (ref "IC9") (pin "4") (pinfunction "GND/NC_4") (pintype "passive"))
      (node (ref "IC9") (pin "6") (pinfunction "GND_6") (pintype "passive"))
      (node (ref "IC9") (pin "7") (pinfunction "GND_7") (pintype "passive"))
      (node (ref "IC9") (pin "9") (pinfunction "DGND_9") (pintype "passive"))
      (node (ref "IC9") (pin "PAD") (pinfunction "PAD_PAD") (pintype "passive"))
      (node (ref "J1") (pin "2") (pinfunction "Y_2") (pintype "passive"))
      (node (ref "J2") (pin "2") (pinfunction "Y_2") (pintype "passive"))
      (node (ref "T1") (pin "2") (pinfunction "2_2") (pintype "passive"))
      (node (ref "T2") (pin "2") (pinfunction "2_2") (pintype "passive"))
      (node (ref "T3") (pin "3") (pinfunction "3_3") (pintype "passive"))
      (node (ref "T4") (pin "3") (pinfunction "3_3") (pintype "passive"))
      (node (ref "T5") (pin "1") (pinfunction "1_1") (pintype "passive"))
      (node (ref "T6") (pin "1") (pinfunction "1_1") (pintype "passive"))
      (node (ref "T7") (pin "2") (pinfunction "2_2") (pintype "passive"))
      (node (ref "T8") (pin "2") (pinfunction "2_2") (pintype "passive"))
    )
    (net (code "50") (name "Net-(C15-Pad2)") (class "Default")
      (node (ref "C15") (pin "2") (pinfunction "2_2") (pintype "passive"))
      (node (ref "T1") (pin "3") (pinfunction "3_3") (pintype "passive"))
    )
    (net (code "51") (name "Net-(C16-Pad2)") (class "Default")
      (node (ref "C16") (pin "2") (pinfunction "2_2") (pintype "passive"))
      (node (ref "T2") (pin "3") (pinfunction "3_3") (pintype "passive"))
    )
    (net (code "52") (name "Net-(C25-Pad2)") (class "Default")
      (node (ref "C25") (pin "2") (pinfunction "2_2") (pintype "passive"))
      (node (ref "T3") (pin "1") (pinfunction "1_1") (pintype "passive"))
    )
    (net (code "53") (name "Net-(C26-Pad2)") (class "Default")
      (node (ref "C26") (pin "2") (pinfunction "2_2") (pintype "passive"))
      (node (ref "T4") (pin "1") (pinfunction "1_1") (pintype "passive"))
    )
    (net (code "54") (name "Net-(C27-Pad2)") (class "Default")
      (node (ref "C27") (pin "2") (pinfunction "2_2") (pintype "passive"))
      (node (ref "T5") (pin "3") (pinfunction "3_3") (pintype "passive"))
    )
    (net (code "55") (name "Net-(C28-Pad2)") (class "Default")
      (node (ref "C28") (pin "2") (pinfunction "2_2") (pintype "passive"))
      (node (ref "T6") (pin "3") (pinfunction "3_3") (pintype "passive"))
    )
    (net (code "56") (name "Net-(C29-Pad2)") (class "Default")
      (node (ref "C29") (pin "2") (pinfunction "2_2") (pintype "passive"))
      (node (ref "T7") (pin "3") (pinfunction "3_3") (pintype "passive"))
    )
    (net (code "57") (name "Net-(C30-Pad2)") (class "Default")
      (node (ref "C30") (pin "2") (pinfunction "2_2") (pintype "passive"))
      (node (ref "T8") (pin "3") (pinfunction "3_3") (pintype "passive"))
    )
    (net (code "58") (name "Net-(IC7-RFC)") (class "Default")
      (node (ref "C31") (pin "1") (pinfunction "1_1") (pintype "passive"))
      (node (ref "IC7") (pin "5") (pinfunction "RFC_5") (pintype "bidirectional"))
    )
    (net (code "59") (name "Net-(IC8-RFC)") (class "Default")
      (node (ref "C32") (pin "2") (pinfunction "2_2") (pintype "passive"))
      (node (ref "IC8") (pin "5") (pinfunction "RFC_5") (pintype "bidirectional"))
    )
    (net (code "60") (name "Net-(IC9-RFC)") (class "Default")
      (node (ref "C37") (pin "1") (pinfunction "1_1") (pintype "passive"))
      (node (ref "IC9") (pin "5") (pinfunction "RFC_5") (pintype "bidirectional"))
    )
    (net (code "61") (name "Net-(IC10-RFC)") (class "Default")
      (node (ref "C38") (pin "2") (pinfunction "2_2") (pintype "passive"))
      (node (ref "IC10") (pin "5") (pinfunction "RFC_5") (pintype "bidirectional"))
    )
    (net (code "62") (name "Net-(MN1-Pad1)") (class "Default")
      (node (ref "MN1") (pin "1") (pinfunction "1_1") (pintype "passive"))
      (node (ref "MN5") (pin "2") (pinfunction "2_2") (pintype "passive"))
    )
    (net (code "63") (name "Net-(MN2-Pad1)") (class "Default")
      (node (ref "MN2") (pin "1") (pinfunction "1_1") (pintype "passive"))
      (node (ref "MN6") (pin "2") (pinfunction "2_2") (pintype "passive"))
    )
    (net (code "64") (name "Net-(MN3-Pad1)") (class "Default")
      (node (ref "MN3") (pin "1") (pinfunction "1_1") (pintype "passive"))
      (node (ref "MN7") (pin "2") (pinfunction "2_2") (pintype "passive"))
    )
    (net (code "65") (name "Net-(MN4-Pad1)") (class "Default")
      (node (ref "MN4") (pin "1") (pinfunction "1_1") (pintype "passive"))
      (node (ref "MN8") (pin "2") (pinfunction "2_2") (pintype "passive"))
    )
    (net (code "66") (name "Net-(MN17-Pad1)") (class "Default")
      (node (ref "MN17") (pin "1") (pinfunction "1_1") (pintype "passive"))
      (node (ref "MN21") (pin "2") (pinfunction "2_2") (pintype "passive"))
    )
    (net (code "67") (name "Net-(MN18-Pad1)") (class "Default")
      (node (ref "MN18") (pin "1") (pinfunction "1_1") (pintype "passive"))
      (node (ref "MN23") (pin "2") (pinfunction "2_2") (pintype "passive"))
    )
    (net (code "68") (name "Net-(MN19-Pad1)") (class "Default")
      (node (ref "MN19") (pin "1") (pinfunction "1_1") (pintype "passive"))
      (node (ref "MN22") (pin "2") (pinfunction "2_2") (pintype "passive"))
    )
    (net (code "69") (name "Net-(MN20-Pad1)") (class "Default")
      (node (ref "MN20") (pin "1") (pinfunction "1_1") (pintype "passive"))
      (node (ref "MN24") (pin "2") (pinfunction "2_2") (pintype "passive"))
    )
    (net (code "70") (name "VCC1P8_LMS1") (class "Default")
      (node (ref "C10") (pin "2") (pinfunction "2_2") (pintype "passive"))
      (node (ref "C11") (pin "2") (pinfunction "2_2") (pintype "passive"))
      (node (ref "C12") (pin "2") (pinfunction "2_2") (pintype "passive"))
      (node (ref "C13") (pin "2") (pinfunction "2_2") (pintype "passive"))
      (node (ref "C14") (pin "2") (pinfunction "2_2") (pintype "passive"))
      (node (ref "C17") (pin "2") (pinfunction "2_2") (pintype "passive"))
      (node (ref "C18") (pin "2") (pinfunction "2_2") (pintype "passive"))
      (node (ref "C19") (pin "2") (pinfunction "2_2") (pintype "passive"))
      (node (ref "C20") (pin "2") (pinfunction "2_2") (pintype "passive"))
      (node (ref "C21") (pin "2") (pinfunction "2_2") (pintype "passive"))
      (node (ref "C22") (pin "2") (pinfunction "2_2") (pintype "passive"))
      (node (ref "C23") (pin "2") (pinfunction "2_2") (pintype "passive"))
      (node (ref "C24") (pin "2") (pinfunction "2_2") (pintype "passive"))
      (node (ref "C7") (pin "2") (pinfunction "2_2") (pintype "passive"))
      (node (ref "C8") (pin "2") (pinfunction "2_2") (pintype "passive"))
      (node (ref "C9") (pin "2") (pinfunction "2_2") (pintype "passive"))
      (node (ref "MN1") (pin "2") (pinfunction "2_2") (pintype "passive"))
      (node (ref "MN17") (pin "2") (pinfunction "2_2") (pintype "passive"))
      (node (ref "MN18") (pin "2") (pinfunction "2_2") (pintype "passive"))
      (node (ref "MN19") (pin "2") (pinfunction "2_2") (pintype "passive"))
      (node (ref "MN2") (pin "2") (pinfunction "2_2") (pintype "passive"))
      (node (ref "MN20") (pin "2") (pinfunction "2_2") (pintype "passive"))
      (node (ref "MN3") (pin "2") (pinfunction "2_2") (pintype "passive"))
      (node (ref "MN4") (pin "2") (pinfunction "2_2") (pintype "passive"))
    )
    (net (code "71") (name "VCC3P3_RF") (class "Default")
      (node (ref "C35") (pin "2") (pinfunction "2_2") (pintype "passive"))
      (node (ref "C36") (pin "2") (pinfunction "2_2") (pintype "passive"))
      (node (ref "C41") (pin "2") (pinfunction "2_2") (pintype "passive"))
      (node (ref "C42") (pin "2") (pinfunction "2_2") (pintype "passive"))
      (node (ref "IC10") (pin "12") (pinfunction "VDD_12") (pintype "power_in"))
      (node (ref "IC7") (pin "12") (pinfunction "VDD_12") (pintype "power_in"))
      (node (ref "IC8") (pin "12") (pinfunction "VDD_12") (pintype "power_in"))
      (node (ref "IC9") (pin "12") (pinfunction "VDD_12") (pintype "power_in"))
    )
    (net (code "72") (name "unconnected-(T3-Pad2)") (class "Default")
      (node (ref "T3") (pin "2") (pinfunction "2_2") (pintype "passive+no_connect"))
    )
    (net (code "73") (name "unconnected-(T4-Pad2)") (class "Default")
      (node (ref "T4") (pin "2") (pinfunction "2_2") (pintype "passive+no_connect"))
    )
    (net (code "74") (name "unconnected-(T5-Pad2)") (class "Default")
      (node (ref "T5") (pin "2") (pinfunction "2_2") (pintype "passive+no_connect"))
    )
    (net (code "75") (name "unconnected-(T6-Pad2)") (class "Default")
      (node (ref "T6") (pin "2") (pinfunction "2_2") (pintype "passive+no_connect"))
    )
  )
)
